# 5-eMMC.net
KiCad netlist of a schematic drawn in Altium Designer
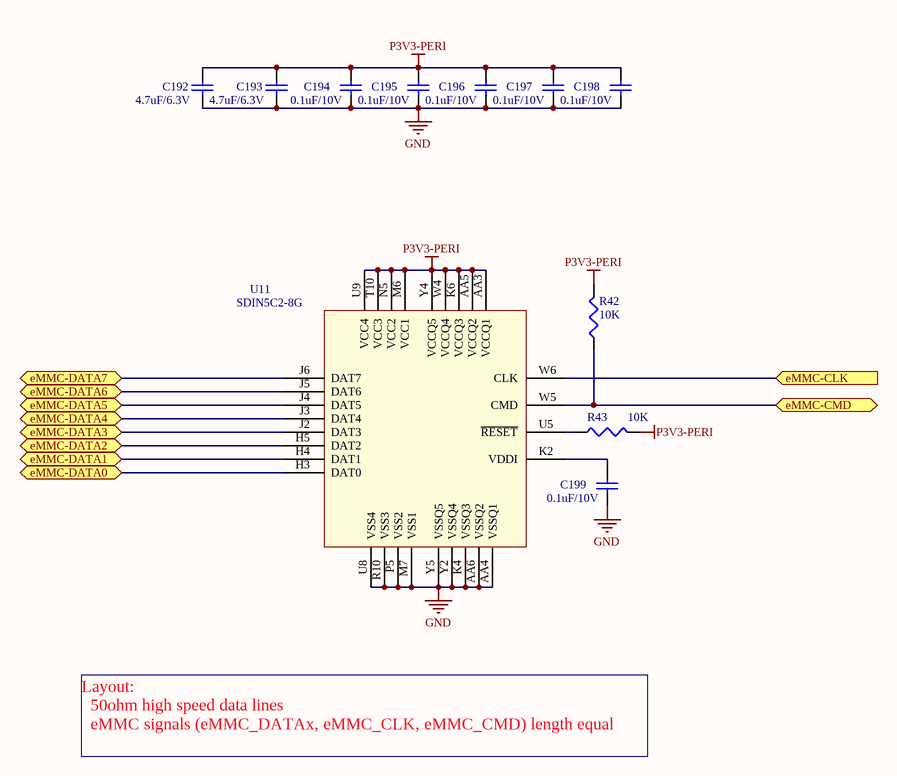
[diagram p0: 5-eMMC.SchDoc]

(export (version "E")
  (design (tool "Eeschema 10.0.6"))
  (components
    (comp (ref "C192")
      (value "4.7uF/6.3V")
      (footprint "0603_CC")
      (description "Capacitor")
      (fields (field (name "PUBLISHER") "Altium Limited"))
      (libsource (lib "Miscellaneous Devices") (part "Cap"))
    )
    (comp (ref "C193")
      (value "4.7uF/6.3V")
      (footprint "0603_CC")
      (description "Capacitor")
      (fields (field (name "PUBLISHER") "Altium Limited"))
      (libsource (lib "Miscellaneous Devices") (part "Cap"))
    )
    (comp (ref "C194")
      (value "0.1uF/10V")
      (footprint "0402_CC")
      (description "Capacitor")
      (fields (field (name "PUBLISHER") "Altium Limited"))
      (libsource (lib "Miscellaneous Devices") (part "Cap"))
    )
    (comp (ref "C195")
      (value "0.1uF/10V")
      (footprint "0402_CC")
      (description "Capacitor")
      (fields (field (name "PUBLISHER") "Altium Limited"))
      (libsource (lib "Miscellaneous Devices") (part "Cap"))
    )
    (comp (ref "C196")
      (value "0.1uF/10V")
      (footprint "0402_CC")
      (description "Capacitor")
      (fields (field (name "PUBLISHER") "Altium Limited"))
      (libsource (lib "Miscellaneous Devices") (part "Cap"))
    )
    (comp (ref "C197")
      (value "0.1uF/10V")
      (footprint "0402_CC")
      (description "Capacitor")
      (fields (field (name "PUBLISHER") "Altium Limited"))
      (libsource (lib "Miscellaneous Devices") (part "Cap"))
    )
    (comp (ref "C198")
      (value "0.1uF/10V")
      (footprint "0402_CC")
      (description "Capacitor")
      (fields (field (name "PUBLISHER") "Altium Limited"))
      (libsource (lib "Miscellaneous Devices") (part "Cap"))
    )
    (comp (ref "C199")
      (value "0.1uF/10V")
      (footprint "0402_CC")
      (description "Capacitor")
      (fields (field (name "PUBLISHER") "Altium Limited"))
      (libsource (lib "Miscellaneous Devices") (part "Cap"))
    )
    (comp (ref "R42")
      (value "10K")
      (footprint "0402_CC")
      (description "Resistor")
      (fields (field (name "PUBLISHER") "Altium Limited"))
      (libsource (lib "Miscellaneous Devices") (part "Res3"))
    )
    (comp (ref "R43")
      (value "10K")
      (footprint "0402_CC")
      (description "Resistor")
      (fields (field (name "PUBLISHER") "Altium Limited"))
      (libsource (lib "Miscellaneous Devices") (part "Res3"))
    )
    (comp (ref "U11")
      (value "SDIN5C2-8G")
      (footprint "BGA169_0P5_12X16")
      (libsource (lib "Schlib") (part "SDIN5C2"))
    )
  )
  (nets
    (net (code "1") (name "/eMMC-CLK") (class "Default")
      (node (ref "U11") (pin "W6") (pinfunction "CLK_W6") (pintype "passive"))
    )
    (net (code "2") (name "/eMMC-CMD") (class "Default")
      (node (ref "R42") (pin "1") (pinfunction "1_1") (pintype "passive"))
      (node (ref "U11") (pin "W5") (pinfunction "CMD_W5") (pintype "passive"))
    )
    (net (code "3") (name "/eMMC-DATA0") (class "Default")
      (node (ref "U11") (pin "H3") (pinfunction "DAT0_H3") (pintype "passive"))
    )
    (net (code "4") (name "/eMMC-DATA1") (class "Default")
      (node (ref "U11") (pin "H4") (pinfunction "DAT1_H4") (pintype "passive"))
    )
    (net (code "5") (name "/eMMC-DATA2") (class "Default")
      (node (ref "U11") (pin "H5") (pinfunction "DAT2_H5") (pintype "passive"))
    )
    (net (code "6") (name "/eMMC-DATA3") (class "Default")
      (node (ref "U11") (pin "J2") (pinfunction "DAT3_J2") (pintype "passive"))
    )
    (net (code "7") (name "/eMMC-DATA4") (class "Default")
      (node (ref "U11") (pin "J3") (pinfunction "DAT4_J3") (pintype "passive"))
    )
    (net (code "8") (name "/eMMC-DATA5") (class "Default")
      (node (ref "U11") (pin "J4") (pinfunction "DAT5_J4") (pintype "passive"))
    )
    (net (code "9") (name "/eMMC-DATA6") (class "Default")
      (node (ref "U11") (pin "J5") (pinfunction "DAT6_J5") (pintype "passive"))
    )
    (net (code "10") (name "/eMMC-DATA7") (class "Default")
      (node (ref "U11") (pin "J6") (pinfunction "DAT7_J6") (pintype "passive"))
    )
    (net (code "11") (name "GND") (class "Default")
      (node (ref "C192") (pin "2") (pinfunction "2_2") (pintype "passive"))
      (node (ref "C193") (pin "2") (pinfunction "2_2") (pintype "passive"))
      (node (ref "C194") (pin "2") (pinfunction "2_2") (pintype "passive"))
      (node (ref "C195") (pin "2") (pinfunction "2_2") (pintype "passive"))
      (node (ref "C196") (pin "2") (pinfunction "2_2") (pintype "passive"))
      (node (ref "C197") (pin "2") (pinfunction "2_2") (pintype "passive"))
      (node (ref "C198") (pin "2") (pinfunction "2_2") (pintype "passive"))
      (node (ref "C199") (pin "2") (pinfunction "2_2") (pintype "passive"))
      (node (ref "U11") (pin "AA4") (pinfunction "VSSQ1_AA4") (pintype "passive"))
      (node (ref "U11") (pin "AA6") (pinfunction "VSSQ2_AA6") (pintype "passive"))
      (node (ref "U11") (pin "K4") (pinfunction "VSSQ3_K4") (pintype "passive"))
      (node (ref "U11") (pin "M7") (pinfunction "VSS1_M7") (pintype "passive"))
      (node (ref "U11") (pin "P5") (pinfunction "VSS2_P5") (pintype "passive"))
      (node (ref "U11") (pin "R10") (pinfunction "VSS3_R10") (pintype "passive"))
      (node (ref "U11") (pin "U8") (pinfunction "VSS4_U8") (pintype "passive"))
      (node (ref "U11") (pin "Y2") (pinfunction "VSSQ4_Y2") (pintype "passive"))
      (node (ref "U11") (pin "Y5") (pinfunction "VSSQ5_Y5") (pintype "passive"))
    )
    (net (code "12") (name "Net-(U11-VDDI)") (class "Default")
      (node (ref "C199") (pin "1") (pinfunction "1_1") (pintype "passive"))
      (node (ref "U11") (pin "K2") (pinfunction "VDDI_K2") (pintype "passive"))
    )
    (net (code "13") (name "Net-(U11-~{RESET})") (class "Default")
      (node (ref "R43") (pin "1") (pinfunction "1_1") (pintype "passive"))
      (node (ref "U11") (pin "U5") (pinfunction "~{RESET}_U5") (pintype "passive"))
    )
    (net (code "14") (name "P3V3-PERI") (class "Default")
      (node (ref "C192") (pin "1") (pinfunction "1_1") (pintype "passive"))
      (node (ref "C193") (pin "1") (pinfunction "1_1") (pintype "passive"))
      (node (ref "C194") (pin "1") (pinfunction "1_1") (pintype "passive"))
      (node (ref "C195") (pin "1") (pinfunction "1_1") (pintype "passive"))
      (node (ref "C196") (pin "1") (pinfunction "1_1") (pintype "passive"))
      (node (ref "C197") (pin "1") (pinfunction "1_1") (pintype "passive"))
      (node (ref "C198") (pin "1") (pinfunction "1_1") (pintype "passive"))
      (node (ref "R42") (pin "2") (pinfunction "2_2") (pintype "passive"))
      (node (ref "R43") (pin "2") (pinfunction "2_2") (pintype "passive"))
      (node (ref "U11") (pin "AA3") (pinfunction "VCCQ1_AA3") (pintype "passive"))
      (node (ref "U11") (pin "AA5") (pinfunction "VCCQ2_AA5") (pintype "passive"))
      (node (ref "U11") (pin "K6") (pinfunction "VCCQ3_K6") (pintype "passive"))
      (node (ref "U11") (pin "M6") (pinfunction "VCC1_M6") (pintype "passive"))
      (node (ref "U11") (pin "N5") (pinfunction "VCC2_N5") (pintype "passive"))
      (node (ref "U11") (pin "T10") (pinfunction "VCC3_T10") (pintype "passive"))
      (node (ref "U11") (pin "U9") (pinfunction "VCC4_U9") (pintype "passive"))
      (node (ref "U11") (pin "W4") (pinfunction "VCCQ4_W4") (pintype "passive"))
      (node (ref "U11") (pin "Y4") (pinfunction "VCCQ5_Y4") (pintype "passive"))
    )
  )
)
